# Programmer.net
KiCad netlist of a schematic drawn in Altium Designer
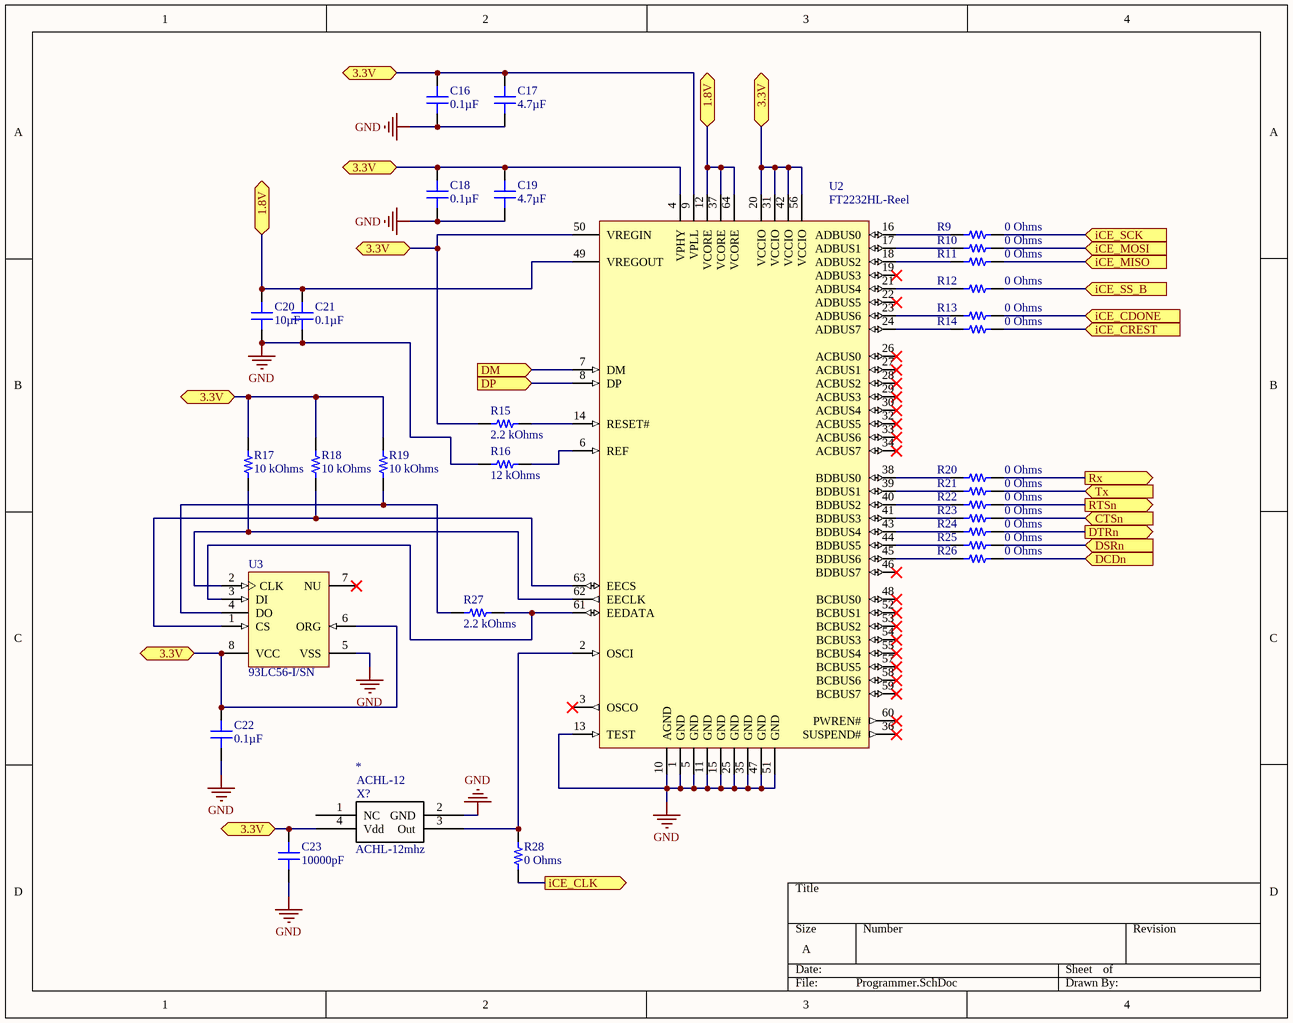
[diagram p0: Programmer.SchDoc]

(export (version "E")
  (design (tool "Eeschema 10.0.6"))
  (components
    (comp (ref "*")
      (value "ACHL-12mhz")
      (footprint "ACHL-12mhz")
      (libsource (lib "2020-09-26_17-27-19") (part "ACHL-12mhz"))
    )
    (comp (ref "C16")
      (value "0.1µF")
      (footprint "CAP 0805_2012")
      (description "CAP CER 0.1UF 50V X7R 0805")
      (fields
        (field (name "PART NUMBER") "CL21B104KBCNNNC")
        (field (name "MANUFACTURER") "Samsung Electro-Mechanics")
      )
      (libsource (lib "Celestial Altium Library - altium_library") (part "Capacitor"))
    )
    (comp (ref "C17")
      (value "4.7µF")
      (footprint "CAP 0805_2012")
      (description "CAP CER 4.7UF 25V X5R 0805")
      (fields
        (field (name "PART NUMBER") "CL21A475KAQNNNE")
        (field (name "MANUFACTURER") "Samsung Electro-Mechanics")
      )
      (libsource (lib "Celestial Altium Library - altium_library") (part "Capacitor"))
    )
    (comp (ref "C18")
      (value "0.1µF")
      (footprint "CAP 0805_2012")
      (description "CAP CER 0.1UF 50V X7R 0805")
      (fields
        (field (name "PART NUMBER") "CL21B104KBCNNNC")
        (field (name "MANUFACTURER") "Samsung Electro-Mechanics")
      )
      (libsource (lib "Celestial Altium Library - altium_library") (part "Capacitor"))
    )
    (comp (ref "C19")
      (value "4.7µF")
      (footprint "CAP 0805_2012")
      (description "CAP CER 4.7UF 25V X5R 0805")
      (fields
        (field (name "PART NUMBER") "CL21A475KAQNNNE")
        (field (name "MANUFACTURER") "Samsung Electro-Mechanics")
      )
      (libsource (lib "Celestial Altium Library - altium_library") (part "Capacitor"))
    )
    (comp (ref "C20")
      (value "10µF")
      (footprint "CAP 0805_2012")
      (description "CAP CER 10UF 16V X5R 0805")
      (fields
        (field (name "PART NUMBER") "CL21A106KOQNNNG")
        (field (name "MANUFACTURER") "Samsung Electro-Mechanics")
      )
      (libsource (lib "Celestial Altium Library - altium_library") (part "Capacitor"))
    )
    (comp (ref "C21")
      (value "0.1µF")
      (footprint "CAP 0805_2012")
      (description "CAP CER 0.1UF 50V X7R 0805")
      (fields
        (field (name "PART NUMBER") "CL21B104KBCNNNC")
        (field (name "MANUFACTURER") "Samsung Electro-Mechanics")
      )
      (libsource (lib "Celestial Altium Library - altium_library") (part "Capacitor"))
    )
    (comp (ref "C22")
      (value "0.1µF")
      (footprint "CAP 0805_2012")
      (description "CAP CER 0.1UF 50V X7R 0805")
      (fields
        (field (name "PART NUMBER") "CL21B104KBCNNNC")
        (field (name "MANUFACTURER") "Samsung Electro-Mechanics")
      )
      (libsource (lib "Celestial Altium Library - altium_library") (part "Capacitor"))
    )
    (comp (ref "C23")
      (value "10000pF")
      (footprint "CAP 0805_2012")
      (description "CAP CER 10000PF 50V X7R 0805")
      (fields
        (field (name "PART NUMBER") "CL21B103KBANNNC")
        (field (name "MANUFACTURER") "Samsung Electro-Mechanics")
      )
      (libsource (lib "Celestial Altium Library - altium_library") (part "Capacitor"))
    )
    (comp (ref "R9")
      (value "0 Ohms")
      (footprint "RES 0805_2012")
      (description "RES 0 OHM JUMPER 1/8W 0805")
      (fields
        (field (name "PART NUMBER") "RMCF0805ZT0R00")
        (field (name "MANUFACTURER") "Stackpole Electronics Inc")
      )
      (libsource (lib "Celestial Altium Library - altium_library") (part "Resistor"))
    )
    (comp (ref "R10")
      (value "0 Ohms")
      (footprint "RES 0805_2012")
      (description "RES 0 OHM JUMPER 1/8W 0805")
      (fields
        (field (name "PART NUMBER") "RMCF0805ZT0R00")
        (field (name "MANUFACTURER") "Stackpole Electronics Inc")
      )
      (libsource (lib "Celestial Altium Library - altium_library") (part "Resistor"))
    )
    (comp (ref "R11")
      (value "0 Ohms")
      (footprint "RES 0805_2012")
      (description "RES 0 OHM JUMPER 1/8W 0805")
      (fields
        (field (name "PART NUMBER") "RMCF0805ZT0R00")
        (field (name "MANUFACTURER") "Stackpole Electronics Inc")
      )
      (libsource (lib "Celestial Altium Library - altium_library") (part "Resistor"))
    )
    (comp (ref "R12")
      (value "0 Ohms")
      (footprint "RES 0805_2012")
      (description "RES 0 OHM JUMPER 1/8W 0805")
      (fields
        (field (name "PART NUMBER") "RMCF0805ZT0R00")
        (field (name "MANUFACTURER") "Stackpole Electronics Inc")
      )
      (libsource (lib "Celestial Altium Library - altium_library") (part "Resistor"))
    )
    (comp (ref "R13")
      (value "0 Ohms")
      (footprint "RES 0805_2012")
      (description "RES 0 OHM JUMPER 1/8W 0805")
      (fields
        (field (name "PART NUMBER") "RMCF0805ZT0R00")
        (field (name "MANUFACTURER") "Stackpole Electronics Inc")
      )
      (libsource (lib "Celestial Altium Library - altium_library") (part "Resistor"))
    )
    (comp (ref "R14")
      (value "0 Ohms")
      (footprint "RES 0805_2012")
      (description "RES 0 OHM JUMPER 1/8W 0805")
      (fields
        (field (name "PART NUMBER") "RMCF0805ZT0R00")
        (field (name "MANUFACTURER") "Stackpole Electronics Inc")
      )
      (libsource (lib "Celestial Altium Library - altium_library") (part "Resistor"))
    )
    (comp (ref "R15")
      (value "2.2 kOhms")
      (footprint "RES 0805_2012")
      (description "RES SMD 2.2K OHM 5% 0.4W 0805")
      (fields (field (name "PART NUMBER") "ESR10EZPJ222") (field (name "MANUFACTURER") "Rohm Semiconductor"))
      (libsource (lib "Celestial Altium Library - altium_library") (part "Resistor"))
    )
    (comp (ref "R16")
      (value "12 kOhms")
      (footprint "RES 0805_2012")
      (description "RES SMD 12K OHM 1% 1/8W 0805")
      (fields
        (field (name "PART NUMBER") "CRG0805F12K")
        (field (name "MANUFACTURER") "TE Connectivity Passive Product")
      )
      (libsource (lib "Celestial Altium Library - altium_library") (part "Resistor"))
    )
    (comp (ref "R17")
      (value "10 kOhms")
      (footprint "RES 0805_2012")
      (description "RES 10K OHM 1% 1/4W 0805")
      (fields
        (field (name "PART NUMBER") "RNCP0805FTD10K0")
        (field (name "MANUFACTURER") "Stackpole Electronics Inc")
      )
      (libsource (lib "Celestial Altium Library - altium_library") (part "Resistor"))
    )
    (comp (ref "R18")
      (value "10 kOhms")
      (footprint "RES 0805_2012")
      (description "RES 10K OHM 1% 1/4W 0805")
      (fields
        (field (name "PART NUMBER") "RNCP0805FTD10K0")
        (field (name "MANUFACTURER") "Stackpole Electronics Inc")
      )
      (libsource (lib "Celestial Altium Library - altium_library") (part "Resistor"))
    )
    (comp (ref "R19")
      (value "10 kOhms")
      (footprint "RES 0805_2012")
      (description "RES 10K OHM 1% 1/4W 0805")
      (fields
        (field (name "PART NUMBER") "RNCP0805FTD10K0")
        (field (name "MANUFACTURER") "Stackpole Electronics Inc")
      )
      (libsource (lib "Celestial Altium Library - altium_library") (part "Resistor"))
    )
    (comp (ref "R20")
      (value "0 Ohms")
      (footprint "RES 0805_2012")
      (description "RES 0 OHM JUMPER 1/8W 0805")
      (fields
        (field (name "PART NUMBER") "RMCF0805ZT0R00")
        (field (name "MANUFACTURER") "Stackpole Electronics Inc")
      )
      (libsource (lib "Celestial Altium Library - altium_library") (part "Resistor"))
    )
    (comp (ref "R21")
      (value "0 Ohms")
      (footprint "RES 0805_2012")
      (description "RES 0 OHM JUMPER 1/8W 0805")
      (fields
        (field (name "PART NUMBER") "RMCF0805ZT0R00")
        (field (name "MANUFACTURER") "Stackpole Electronics Inc")
      )
      (libsource (lib "Celestial Altium Library - altium_library") (part "Resistor"))
    )
    (comp (ref "R22")
      (value "0 Ohms")
      (footprint "RES 0805_2012")
      (description "RES 0 OHM JUMPER 1/8W 0805")
      (fields
        (field (name "PART NUMBER") "RMCF0805ZT0R00")
        (field (name "MANUFACTURER") "Stackpole Electronics Inc")
      )
      (libsource (lib "Celestial Altium Library - altium_library") (part "Resistor"))
    )
    (comp (ref "R23")
      (value "0 Ohms")
      (footprint "RES 0805_2012")
      (description "RES 0 OHM JUMPER 1/8W 0805")
      (fields
        (field (name "PART NUMBER") "RMCF0805ZT0R00")
        (field (name "MANUFACTURER") "Stackpole Electronics Inc")
      )
      (libsource (lib "Celestial Altium Library - altium_library") (part "Resistor"))
    )
    (comp (ref "R24")
      (value "0 Ohms")
      (footprint "RES 0805_2012")
      (description "RES 0 OHM JUMPER 1/8W 0805")
      (fields
        (field (name "PART NUMBER") "RMCF0805ZT0R00")
        (field (name "MANUFACTURER") "Stackpole Electronics Inc")
      )
      (libsource (lib "Celestial Altium Library - altium_library") (part "Resistor"))
    )
    (comp (ref "R25")
      (value "0 Ohms")
      (footprint "RES 0805_2012")
      (description "RES 0 OHM JUMPER 1/8W 0805")
      (fields
        (field (name "PART NUMBER") "RMCF0805ZT0R00")
        (field (name "MANUFACTURER") "Stackpole Electronics Inc")
      )
      (libsource (lib "Celestial Altium Library - altium_library") (part "Resistor"))
    )
    (comp (ref "R26")
      (value "0 Ohms")
      (footprint "RES 0805_2012")
      (description "RES 0 OHM JUMPER 1/8W 0805")
      (fields
        (field (name "PART NUMBER") "RMCF0805ZT0R00")
        (field (name "MANUFACTURER") "Stackpole Electronics Inc")
      )
      (libsource (lib "Celestial Altium Library - altium_library") (part "Resistor"))
    )
    (comp (ref "R27")
      (value "2.2 kOhms")
      (footprint "RES 0805_2012")
      (description "RES SMD 2.2K OHM 5% 0.4W 0805")
      (fields (field (name "PART NUMBER") "ESR10EZPJ222") (field (name "MANUFACTURER") "Rohm Semiconductor"))
      (libsource (lib "Celestial Altium Library - altium_library") (part "Resistor"))
    )
    (comp (ref "R28")
      (value "0 Ohms")
      (footprint "RES 0805_2012")
      (description "RES 0 OHM JUMPER 1/8W 0805")
      (fields
        (field (name "PART NUMBER") "RMCF0805ZT0R00")
        (field (name "MANUFACTURER") "Stackpole Electronics Inc")
      )
      (libsource (lib "Celestial Altium Library - altium_library") (part "Resistor"))
    )
    (comp (ref "U2")
      (value "FT2232HL-Reel")
      (footprint "LQFP-64_M")
      (description "Dual High Speed USB To Multipurpose UART/FIFO IC, 64-pin LQFP, Tape and Reel")
      (fields (field (name "MANUFACTURER") "FTDI"))
      (libsource (lib "Altium Content Vault") (part "COM-UART-FT2232H-LQFP64"))
    )
    (comp (ref "U3")
      (value "93LC56-I/SN")
      (footprint "MCHP-SOIC-SN8_N")
      (description "2K bits Microwire Serial EEPROM, 2.5 to 5.5 V, 2 MHz, -40 to 85 degC, 8-pin SOIC (SN8), Tube")
      (fields (field (name "MANUFACTURER") "Microchip"))
      (libsource (lib "Altium Content Vault") (part "MCHP-93LC46-56-66-AA56-66-SOIC-PDIP-8"))
    )
  )
  (nets
    (net (code "1") (name "/1.8V") (class "Default")
      (node (ref "C20") (pin "2") (pinfunction "2_2") (pintype "passive"))
      (node (ref "C21") (pin "2") (pinfunction "2_2") (pintype "passive"))
      (node (ref "U2") (pin "12") (pinfunction "VCORE_12") (pintype "power_in"))
      (node (ref "U2") (pin "37") (pinfunction "VCORE_37") (pintype "power_in"))
      (node (ref "U2") (pin "49") (pinfunction "VREGOUT_49") (pintype "power_in"))
      (node (ref "U2") (pin "64") (pinfunction "VCORE_64") (pintype "power_in"))
    )
    (net (code "2") (name "/3.3V") (class "Default")
      (node (ref "*") (pin "4") (pinfunction "Vdd_4") (pintype "passive"))
      (node (ref "C16") (pin "2") (pinfunction "2_2") (pintype "passive"))
      (node (ref "C17") (pin "2") (pinfunction "2_2") (pintype "passive"))
      (node (ref "C18") (pin "2") (pinfunction "2_2") (pintype "passive"))
      (node (ref "C19") (pin "2") (pinfunction "2_2") (pintype "passive"))
      (node (ref "C22") (pin "2") (pinfunction "2_2") (pintype "passive"))
      (node (ref "C23") (pin "2") (pinfunction "2_2") (pintype "passive"))
      (node (ref "R15") (pin "1") (pinfunction "1_1") (pintype "passive"))
      (node (ref "R17") (pin "2") (pinfunction "2_2") (pintype "passive"))
      (node (ref "R18") (pin "2") (pinfunction "2_2") (pintype "passive"))
      (node (ref "R19") (pin "2") (pinfunction "2_2") (pintype "passive"))
      (node (ref "U2") (pin "20") (pinfunction "VCCIO_20") (pintype "power_in"))
      (node (ref "U2") (pin "31") (pinfunction "VCCIO_31") (pintype "power_in"))
      (node (ref "U2") (pin "4") (pinfunction "VPHY_4") (pintype "power_in"))
      (node (ref "U2") (pin "42") (pinfunction "VCCIO_42") (pintype "power_in"))
      (node (ref "U2") (pin "50") (pinfunction "VREGIN_50") (pintype "power_in"))
      (node (ref "U2") (pin "56") (pinfunction "VCCIO_56") (pintype "power_in"))
      (node (ref "U2") (pin "9") (pinfunction "VPLL_9") (pintype "power_in"))
      (node (ref "U3") (pin "6") (pinfunction "ORG_6") (pintype "input"))
      (node (ref "U3") (pin "8") (pinfunction "VCC_8") (pintype "power_in"))
    )
    (net (code "3") (name "/CTSn") (class "Default")
      (node (ref "R23") (pin "1") (pinfunction "1_1") (pintype "passive"))
    )
    (net (code "4") (name "/DCDn") (class "Default")
      (node (ref "R26") (pin "1") (pinfunction "1_1") (pintype "passive"))
    )
    (net (code "5") (name "/DM") (class "Default")
      (node (ref "U2") (pin "7") (pinfunction "DM_7") (pintype "input"))
    )
    (net (code "6") (name "/DP") (class "Default")
      (node (ref "U2") (pin "8") (pinfunction "DP_8") (pintype "input"))
    )
    (net (code "7") (name "/DSRn") (class "Default")
      (node (ref "R25") (pin "1") (pinfunction "1_1") (pintype "passive"))
    )
    (net (code "8") (name "/DTRn") (class "Default")
      (node (ref "R24") (pin "1") (pinfunction "1_1") (pintype "passive"))
    )
    (net (code "9") (name "/RTSn") (class "Default")
      (node (ref "R22") (pin "1") (pinfunction "1_1") (pintype "passive"))
    )
    (net (code "10") (name "/Rx") (class "Default")
      (node (ref "R20") (pin "1") (pinfunction "1_1") (pintype "passive"))
    )
    (net (code "11") (name "/Tx") (class "Default")
      (node (ref "R21") (pin "1") (pinfunction "1_1") (pintype "passive"))
    )
    (net (code "12") (name "/iCE_CDONE") (class "Default")
      (node (ref "R13") (pin "1") (pinfunction "1_1") (pintype "passive"))
    )
    (net (code "13") (name "/iCE_CLK") (class "Default")
      (node (ref "R28") (pin "1") (pinfunction "1_1") (pintype "passive"))
    )
    (net (code "14") (name "/iCE_CREST") (class "Default")
      (node (ref "R14") (pin "1") (pinfunction "1_1") (pintype "passive"))
    )
    (net (code "15") (name "/iCE_MISO") (class "Default")
      (node (ref "R11") (pin "1") (pinfunction "1_1") (pintype "passive"))
    )
    (net (code "16") (name "/iCE_MOSI") (class "Default")
      (node (ref "R10") (pin "1") (pinfunction "1_1") (pintype "passive"))
    )
    (net (code "17") (name "/iCE_SCK") (class "Default")
      (node (ref "R9") (pin "1") (pinfunction "1_1") (pintype "passive"))
    )
    (net (code "18") (name "/iCE_SS_B") (class "Default")
      (node (ref "R12") (pin "1") (pinfunction "1_1") (pintype "passive"))
    )
    (net (code "19") (name "GND") (class "Default")
      (node (ref "*") (pin "2") (pinfunction "GND_2") (pintype "passive"))
      (node (ref "C16") (pin "1") (pinfunction "1_1") (pintype "passive"))
      (node (ref "C17") (pin "1") (pinfunction "1_1") (pintype "passive"))
      (node (ref "C18") (pin "1") (pinfunction "1_1") (pintype "passive"))
      (node (ref "C19") (pin "1") (pinfunction "1_1") (pintype "passive"))
      (node (ref "C20") (pin "1") (pinfunction "1_1") (pintype "passive"))
      (node (ref "C21") (pin "1") (pinfunction "1_1") (pintype "passive"))
      (node (ref "C22") (pin "1") (pinfunction "1_1") (pintype "passive"))
      (node (ref "C23") (pin "1") (pinfunction "1_1") (pintype "passive"))
      (node (ref "R16") (pin "1") (pinfunction "1_1") (pintype "passive"))
      (node (ref "U2") (pin "1") (pinfunction "GND_1") (pintype "power_in"))
      (node (ref "U2") (pin "10") (pinfunction "AGND_10") (pintype "power_in"))
      (node (ref "U2") (pin "11") (pinfunction "GND_11") (pintype "power_in"))
      (node (ref "U2") (pin "13") (pinfunction "TEST_13") (pintype "input"))
      (node (ref "U2") (pin "15") (pinfunction "GND_15") (pintype "power_in"))
      (node (ref "U2") (pin "25") (pinfunction "GND_25") (pintype "power_in"))
      (node (ref "U2") (pin "35") (pinfunction "GND_35") (pintype "power_in"))
      (node (ref "U2") (pin "47") (pinfunction "GND_47") (pintype "power_in"))
      (node (ref "U2") (pin "5") (pinfunction "GND_5") (pintype "power_in"))
      (node (ref "U2") (pin "51") (pinfunction "GND_51") (pintype "power_in"))
      (node (ref "U3") (pin "5") (pinfunction "VSS_5") (pintype "power_in"))
    )
    (net (code "20") (name "Net-(*-Out)") (class "Default")
      (node (ref "*") (pin "3") (pinfunction "Out_3") (pintype "passive"))
      (node (ref "R28") (pin "2") (pinfunction "2_2") (pintype "passive"))
      (node (ref "U2") (pin "2") (pinfunction "OSCI_2") (pintype "input"))
    )
    (net (code "21") (name "Net-(U2-ADBUS0)") (class "Default")
      (node (ref "R9") (pin "2") (pinfunction "2_2") (pintype "passive"))
      (node (ref "U2") (pin "16") (pinfunction "ADBUS0_16") (pintype "bidirectional"))
    )
    (net (code "22") (name "Net-(U2-ADBUS1)") (class "Default")
      (node (ref "R10") (pin "2") (pinfunction "2_2") (pintype "passive"))
      (node (ref "U2") (pin "17") (pinfunction "ADBUS1_17") (pintype "bidirectional"))
    )
    (net (code "23") (name "Net-(U2-ADBUS2)") (class "Default")
      (node (ref "R11") (pin "2") (pinfunction "2_2") (pintype "passive"))
      (node (ref "U2") (pin "18") (pinfunction "ADBUS2_18") (pintype "bidirectional"))
    )
    (net (code "24") (name "Net-(U2-ADBUS4)") (class "Default")
      (node (ref "R12") (pin "2") (pinfunction "2_2") (pintype "passive"))
      (node (ref "U2") (pin "21") (pinfunction "ADBUS4_21") (pintype "bidirectional"))
    )
    (net (code "25") (name "Net-(U2-ADBUS6)") (class "Default")
      (node (ref "R13") (pin "2") (pinfunction "2_2") (pintype "passive"))
      (node (ref "U2") (pin "23") (pinfunction "ADBUS6_23") (pintype "bidirectional"))
    )
    (net (code "26") (name "Net-(U2-ADBUS7)") (class "Default")
      (node (ref "R14") (pin "2") (pinfunction "2_2") (pintype "passive"))
      (node (ref "U2") (pin "24") (pinfunction "ADBUS7_24") (pintype "bidirectional"))
    )
    (net (code "27") (name "Net-(U2-BDBUS0)") (class "Default")
      (node (ref "R20") (pin "2") (pinfunction "2_2") (pintype "passive"))
      (node (ref "U2") (pin "38") (pinfunction "BDBUS0_38") (pintype "bidirectional"))
    )
    (net (code "28") (name "Net-(U2-BDBUS1)") (class "Default")
      (node (ref "R21") (pin "2") (pinfunction "2_2") (pintype "passive"))
      (node (ref "U2") (pin "39") (pinfunction "BDBUS1_39") (pintype "bidirectional"))
    )
    (net (code "29") (name "Net-(U2-BDBUS2)") (class "Default")
      (node (ref "R22") (pin "2") (pinfunction "2_2") (pintype "passive"))
      (node (ref "U2") (pin "40") (pinfunction "BDBUS2_40") (pintype "bidirectional"))
    )
    (net (code "30") (name "Net-(U2-BDBUS3)") (class "Default")
      (node (ref "R23") (pin "2") (pinfunction "2_2") (pintype "passive"))
      (node (ref "U2") (pin "41") (pinfunction "BDBUS3_41") (pintype "bidirectional"))
    )
    (net (code "31") (name "Net-(U2-BDBUS4)") (class "Default")
      (node (ref "R24") (pin "2") (pinfunction "2_2") (pintype "passive"))
      (node (ref "U2") (pin "43") (pinfunction "BDBUS4_43") (pintype "bidirectional"))
    )
    (net (code "32") (name "Net-(U2-BDBUS5)") (class "Default")
      (node (ref "R25") (pin "2") (pinfunction "2_2") (pintype "passive"))
      (node (ref "U2") (pin "44") (pinfunction "BDBUS5_44") (pintype "bidirectional"))
    )
    (net (code "33") (name "Net-(U2-BDBUS6)") (class "Default")
      (node (ref "R26") (pin "2") (pinfunction "2_2") (pintype "passive"))
      (node (ref "U2") (pin "45") (pinfunction "BDBUS6_45") (pintype "bidirectional"))
    )
    (net (code "34") (name "Net-(U2-EECLK)") (class "Default")
      (node (ref "R17") (pin "1") (pinfunction "1_1") (pintype "passive"))
      (node (ref "U2") (pin "62") (pinfunction "EECLK_62") (pintype "output"))
      (node (ref "U3") (pin "2") (pinfunction "CLK_2") (pintype "input"))
    )
    (net (code "35") (name "Net-(U2-EECS)") (class "Default")
      (node (ref "R18") (pin "1") (pinfunction "1_1") (pintype "passive"))
      (node (ref "U2") (pin "63") (pinfunction "EECS_63") (pintype "bidirectional"))
      (node (ref "U3") (pin "1") (pinfunction "CS_1") (pintype "input"))
    )
    (net (code "36") (name "Net-(U2-EEDATA)") (class "Default")
      (node (ref "R27") (pin "2") (pinfunction "2_2") (pintype "passive"))
      (node (ref "U2") (pin "61") (pinfunction "EEDATA_61") (pintype "bidirectional"))
      (node (ref "U3") (pin "3") (pinfunction "DI_3") (pintype "input"))
    )
    (net (code "37") (name "Net-(U2-REF)") (class "Default")
      (node (ref "R16") (pin "2") (pinfunction "2_2") (pintype "passive"))
      (node (ref "U2") (pin "6") (pinfunction "REF_6") (pintype "input"))
    )
    (net (code "38") (name "Net-(U2-RESET#)") (class "Default")
      (node (ref "R15") (pin "2") (pinfunction "2_2") (pintype "passive"))
      (node (ref "U2") (pin "14") (pinfunction "RESET#_14") (pintype "input"))
    )
    (net (code "39") (name "Net-(U3-DO)") (class "Default")
      (node (ref "R19") (pin "1") (pinfunction "1_1") (pintype "passive"))
      (node (ref "R27") (pin "1") (pinfunction "1_1") (pintype "passive"))
      (node (ref "U3") (pin "4") (pinfunction "DO_4") (pintype "tri_state"))
    )
    (net (code "40") (name "unconnected-(*-NC-Pad1)") (class "Default")
      (node (ref "*") (pin "1") (pinfunction "NC_1") (pintype "passive"))
    )
    (net (code "41") (name "unconnected-(U2-ACBUS0-Pad26)") (class "Default")
      (node (ref "U2") (pin "26") (pinfunction "ACBUS0_26") (pintype "bidirectional+no_connect"))
    )
    (net (code "42") (name "unconnected-(U2-ACBUS1-Pad27)") (class "Default")
      (node (ref "U2") (pin "27") (pinfunction "ACBUS1_27") (pintype "bidirectional+no_connect"))
    )
    (net (code "43") (name "unconnected-(U2-ACBUS2-Pad28)") (class "Default")
      (node (ref "U2") (pin "28") (pinfunction "ACBUS2_28") (pintype "bidirectional+no_connect"))
    )
    (net (code "44") (name "unconnected-(U2-ACBUS3-Pad29)") (class "Default")
      (node (ref "U2") (pin "29") (pinfunction "ACBUS3_29") (pintype "bidirectional+no_connect"))
    )
    (net (code "45") (name "unconnected-(U2-ACBUS4-Pad30)") (class "Default")
      (node (ref "U2") (pin "30") (pinfunction "ACBUS4_30") (pintype "bidirectional+no_connect"))
    )
    (net (code "46") (name "unconnected-(U2-ACBUS5-Pad32)") (class "Default")
      (node (ref "U2") (pin "32") (pinfunction "ACBUS5_32") (pintype "bidirectional+no_connect"))
    )
    (net (code "47") (name "unconnected-(U2-ACBUS6-Pad33)") (class "Default")
      (node (ref "U2") (pin "33") (pinfunction "ACBUS6_33") (pintype "bidirectional+no_connect"))
    )
    (net (code "48") (name "unconnected-(U2-ACBUS7-Pad34)") (class "Default")
      (node (ref "U2") (pin "34") (pinfunction "ACBUS7_34") (pintype "bidirectional+no_connect"))
    )
    (net (code "49") (name "unconnected-(U2-ADBUS3-Pad19)") (class "Default")
      (node (ref "U2") (pin "19") (pinfunction "ADBUS3_19") (pintype "bidirectional+no_connect"))
    )
    (net (code "50") (name "unconnected-(U2-ADBUS5-Pad22)") (class "Default")
      (node (ref "U2") (pin "22") (pinfunction "ADBUS5_22") (pintype "bidirectional+no_connect"))
    )
    (net (code "51") (name "unconnected-(U2-BCBUS0-Pad48)") (class "Default")
      (node (ref "U2") (pin "48") (pinfunction "BCBUS0_48") (pintype "bidirectional+no_connect"))
    )
    (net (code "52") (name "unconnected-(U2-BCBUS1-Pad52)") (class "Default")
      (node (ref "U2") (pin "52") (pinfunction "BCBUS1_52") (pintype "bidirectional+no_connect"))
    )
    (net (code "53") (name "unconnected-(U2-BCBUS2-Pad53)") (class "Default")
      (node (ref "U2") (pin "53") (pinfunction "BCBUS2_53") (pintype "bidirectional+no_connect"))
    )
    (net (code "54") (name "unconnected-(U2-BCBUS3-Pad54)") (class "Default")
      (node (ref "U2") (pin "54") (pinfunction "BCBUS3_54") (pintype "bidirectional+no_connect"))
    )
    (net (code "55") (name "unconnected-(U2-BCBUS4-Pad55)") (class "Default")
      (node (ref "U2") (pin "55") (pinfunction "BCBUS4_55") (pintype "bidirectional+no_connect"))
    )
    (net (code "56") (name "unconnected-(U2-BCBUS5-Pad57)") (class "Default")
      (node (ref "U2") (pin "57") (pinfunction "BCBUS5_57") (pintype "bidirectional+no_connect"))
    )
    (net (code "57") (name "unconnected-(U2-BCBUS6-Pad58)") (class "Default")
      (node (ref "U2") (pin "58") (pinfunction "BCBUS6_58") (pintype "bidirectional+no_connect"))
    )
    (net (code "58") (name "unconnected-(U2-BCBUS7-Pad59)") (class "Default")
      (node (ref "U2") (pin "59") (pinfunction "BCBUS7_59") (pintype "bidirectional+no_connect"))
    )
    (net (code "59") (name "unconnected-(U2-BDBUS7-Pad46)") (class "Default")
      (node (ref "U2") (pin "46") (pinfunction "BDBUS7_46") (pintype "bidirectional+no_connect"))
    )
    (net (code "60") (name "unconnected-(U2-OSCO-Pad3)") (class "Default")
      (node (ref "U2") (pin "3") (pinfunction "OSCO_3") (pintype "output+no_connect"))
    )
    (net (code "61") (name "unconnected-(U2-PWREN#-Pad60)") (class "Default")
      (node (ref "U2") (pin "60") (pinfunction "PWREN#_60") (pintype "output+no_connect"))
    )
    (net (code "62") (name "unconnected-(U2-SUSPEND#-Pad36)") (class "Default")
      (node (ref "U2") (pin "36") (pinfunction "SUSPEND#_36") (pintype "output+no_connect"))
    )
    (net (code "63") (name "unconnected-(U3-NU-Pad7)") (class "Default")
      (node (ref "U3") (pin "7") (pinfunction "NU_7") (pintype "passive+no_connect"))
    )
  )
)
